# riffle-CTL-0_2-dip.net
KiCad netlist of a schematic drawn in EAGLE
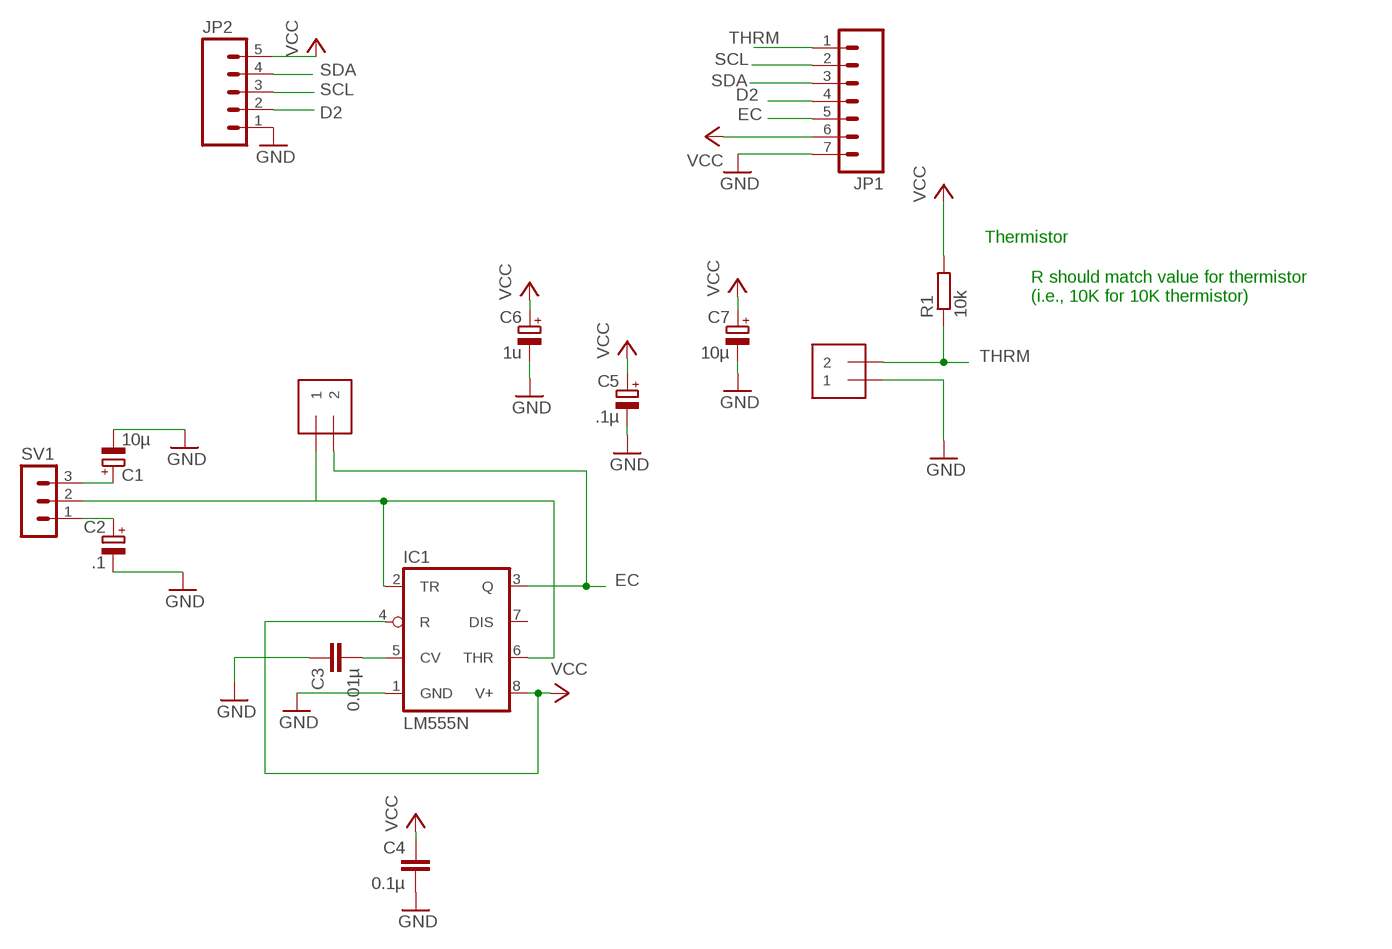
[diagram p0: schematic, sheet 1]

(export (version "E")
  (design (tool "Eeschema 10.0.6"))
  (components
    (comp (ref "C1")
      (value "10µ")
      (footprint "eagle-import:E1,8-4")
      (libsource (lib "eagle-import") (part "CPOL-EUE1.8-4"))
    )
    (comp (ref "C2")
      (value ".1")
      (footprint "eagle-import:E1,8-4")
      (libsource (lib "eagle-import") (part "CPOL-EUE1.8-4"))
    )
    (comp (ref "C3")
      (value "0.01µ")
      (footprint "eagle-import:C025-024X044")
      (libsource (lib "eagle-import") (part "C-EU025-024X044"))
    )
    (comp (ref "C4")
      (value "0.1µ")
      (footprint "eagle-import:C025-024X044")
      (libsource (lib "eagle-import") (part "C-EU025-024X044"))
    )
    (comp (ref "C5")
      (value ".1µ")
      (footprint "eagle-import:E1,8-4")
      (libsource (lib "eagle-import") (part "CPOL-EUE1.8-4"))
    )
    (comp (ref "C6")
      (value "1u")
      (footprint "eagle-import:E1,8-4")
      (libsource (lib "eagle-import") (part "CPOL-EUE1.8-4"))
    )
    (comp (ref "C7")
      (value "10µ")
      (footprint "eagle-import:E1,8-4")
      (libsource (lib "eagle-import") (part "CPOL-EUE1.8-4"))
    )
    (comp (ref "EC1")
      (value "1X2-3.5MM")
      (footprint "eagle-import:1X2-3.5MM")
      (libsource (lib "eagle-import") (part "1X2-3.5MM"))
    )
    (comp (ref "IC1")
      (value "LM555N")
      (footprint "eagle-import:DIL08")
      (libsource (lib "eagle-import") (part "555NLM"))
    )
    (comp (ref "JP1")
      (value "M07")
      (footprint "eagle-import:1X07")
      (libsource (lib "eagle-import") (part "M07"))
    )
    (comp (ref "JP2")
      (value "M05PTH")
      (footprint "eagle-import:1X05")
      (libsource (lib "eagle-import") (part "M05PTH"))
    )
    (comp (ref "R1")
      (value "10k")
      (footprint "eagle-import:0204_7")
      (libsource (lib "eagle-import") (part "R-EU_0204/7"))
    )
    (comp (ref "SV1")
      (value "MA03-1")
      (footprint "eagle-import:MA03-1")
      (libsource (lib "eagle-import") (part "MA03-1"))
    )
    (comp (ref "THRM")
      (value "1X2-3.5MM")
      (footprint "eagle-import:1X2-3.5MM")
      (libsource (lib "eagle-import") (part "1X2-3.5MM"))
    )
  )
  (nets
    (net (code "1") (name "/D2") (class "Default")
      (node (ref "JP1") (pin "4") (pinfunction "4_4") (pintype "passive"))
      (node (ref "JP2") (pin "2") (pinfunction "2_2") (pintype "passive"))
    )
    (net (code "2") (name "/EC") (class "Default")
      (node (ref "EC1") (pin "2") (pinfunction "2_2") (pintype "passive"))
      (node (ref "IC1") (pin "3") (pinfunction "Q_3") (pintype "output"))
      (node (ref "JP1") (pin "5") (pinfunction "5_5") (pintype "passive"))
    )
    (net (code "3") (name "/SCL") (class "Default")
      (node (ref "JP1") (pin "2") (pinfunction "2_2") (pintype "passive"))
      (node (ref "JP2") (pin "3") (pinfunction "3_3") (pintype "passive"))
    )
    (net (code "4") (name "/SDA") (class "Default")
      (node (ref "JP1") (pin "3") (pinfunction "3_3") (pintype "passive"))
      (node (ref "JP2") (pin "4") (pinfunction "4_4") (pintype "passive"))
    )
    (net (code "5") (name "/THRM") (class "Default")
      (node (ref "JP1") (pin "1") (pinfunction "1_1") (pintype "passive"))
      (node (ref "R1") (pin "1") (pinfunction "1_1") (pintype "passive"))
      (node (ref "THRM") (pin "2") (pinfunction "2_2") (pintype "passive"))
    )
    (net (code "6") (name "GND") (class "Default")
      (node (ref "C1") (pin "-") (pinfunction "-_-") (pintype "passive"))
      (node (ref "C2") (pin "-") (pinfunction "-_-") (pintype "passive"))
      (node (ref "C3") (pin "1") (pinfunction "1_1") (pintype "passive"))
      (node (ref "C4") (pin "2") (pinfunction "2_2") (pintype "passive"))
      (node (ref "C5") (pin "-") (pinfunction "-_-") (pintype "passive"))
      (node (ref "C6") (pin "-") (pinfunction "-_-") (pintype "passive"))
      (node (ref "C7") (pin "-") (pinfunction "-_-") (pintype "passive"))
      (node (ref "IC1") (pin "1") (pinfunction "GND_1") (pintype "power_in"))
      (node (ref "JP1") (pin "7") (pinfunction "7_7") (pintype "passive"))
      (node (ref "JP2") (pin "1") (pinfunction "1_1") (pintype "passive"))
      (node (ref "THRM") (pin "1") (pinfunction "1_1") (pintype "passive"))
    )
    (net (code "7") (name "Net-(C1-Pad+)") (class "Default")
      (node (ref "C1") (pin "+") (pinfunction "+_+") (pintype "passive"))
      (node (ref "SV1") (pin "3") (pinfunction "3_3") (pintype "passive"))
    )
    (net (code "8") (name "Net-(C2-Pad+)") (class "Default")
      (node (ref "C2") (pin "+") (pinfunction "+_+") (pintype "passive"))
      (node (ref "SV1") (pin "1") (pinfunction "1_1") (pintype "passive"))
    )
    (net (code "9") (name "Net-(IC1-CV)") (class "Default")
      (node (ref "C3") (pin "2") (pinfunction "2_2") (pintype "passive"))
      (node (ref "IC1") (pin "5") (pinfunction "CV_5") (pintype "input"))
    )
    (net (code "10") (name "Net-(IC1-THR)") (class "Default")
      (node (ref "EC1") (pin "1") (pinfunction "1_1") (pintype "passive"))
      (node (ref "IC1") (pin "2") (pinfunction "TR_2") (pintype "input"))
      (node (ref "IC1") (pin "6") (pinfunction "THR_6") (pintype "input"))
      (node (ref "SV1") (pin "2") (pinfunction "2_2") (pintype "passive"))
    )
    (net (code "11") (name "VCC") (class "Default")
      (node (ref "C4") (pin "1") (pinfunction "1_1") (pintype "passive"))
      (node (ref "C5") (pin "+") (pinfunction "+_+") (pintype "passive"))
      (node (ref "C6") (pin "+") (pinfunction "+_+") (pintype "passive"))
      (node (ref "C7") (pin "+") (pinfunction "+_+") (pintype "passive"))
      (node (ref "IC1") (pin "4") (pinfunction "R_4") (pintype "input"))
      (node (ref "IC1") (pin "8") (pinfunction "V+_8") (pintype "power_in"))
      (node (ref "JP1") (pin "6") (pinfunction "6_6") (pintype "passive"))
      (node (ref "JP2") (pin "5") (pinfunction "5_5") (pintype "passive"))
      (node (ref "R1") (pin "2") (pinfunction "2_2") (pintype "passive"))
    )
    (net (code "12") (name "unconnected-(IC1-DIS-Pad7)") (class "Default")
      (node (ref "IC1") (pin "7") (pinfunction "DIS_7") (pintype "input"))
    )
  )
)
